# RS232.net
KiCad netlist of a schematic drawn in Altium Designer
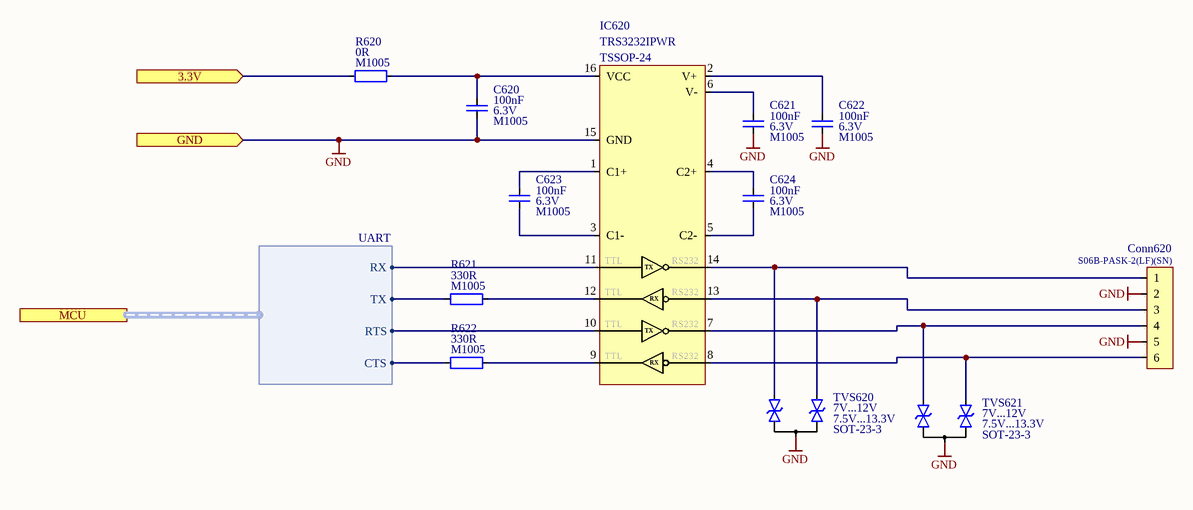
[diagram p0: RS232.SchDoc]

(export (version "E")
  (design (tool "Eeschema 10.0.6"))
  (components
    (comp (ref "C620")
      (value "100nF")
      (footprint "Capacitor_Ceramic_M1005_I0402")
      (description "Cap, Cer, 100nF, 6.3V, M1005")
      (fields
        (field (name "VOLTAGE") "6.3V")
        (field (name "MANUFACTURER PART NUMBER") "04026D104KAT4A")
        (field (name "MANUFACTURER") "Kyocera")
        (field (name "PACKAGE") "M1005")
      )
      (libsource (lib "Capacitor") (part "Capacitor_Ceramic"))
    )
    (comp (ref "C621")
      (value "100nF")
      (footprint "Capacitor_Ceramic_M1005_I0402")
      (description "Cap, Cer, 100nF, 6.3V, M1005")
      (fields
        (field (name "VOLTAGE") "6.3V")
        (field (name "MANUFACTURER PART NUMBER") "04026D104KAT4A")
        (field (name "MANUFACTURER") "Kyocera")
        (field (name "PACKAGE") "M1005")
      )
      (libsource (lib "Capacitor") (part "Capacitor_Ceramic"))
    )
    (comp (ref "C622")
      (value "100nF")
      (footprint "Capacitor_Ceramic_M1005_I0402")
      (description "Cap, Cer, 100nF, 6.3V, M1005")
      (fields
        (field (name "VOLTAGE") "6.3V")
        (field (name "MANUFACTURER PART NUMBER") "04026D104KAT4A")
        (field (name "MANUFACTURER") "Kyocera")
        (field (name "PACKAGE") "M1005")
      )
      (libsource (lib "Capacitor") (part "Capacitor_Ceramic"))
    )
    (comp (ref "C623")
      (value "100nF")
      (footprint "Capacitor_Ceramic_M1005_I0402")
      (description "Cap, Cer, 100nF, 6.3V, M1005")
      (fields
        (field (name "VOLTAGE") "6.3V")
        (field (name "MANUFACTURER PART NUMBER") "04026D104KAT4A")
        (field (name "MANUFACTURER") "Kyocera")
        (field (name "PACKAGE") "M1005")
      )
      (libsource (lib "Capacitor") (part "Capacitor_Ceramic"))
    )
    (comp (ref "C624")
      (value "100nF")
      (footprint "Capacitor_Ceramic_M1005_I0402")
      (description "Cap, Cer, 100nF, 6.3V, M1005")
      (fields
        (field (name "VOLTAGE") "6.3V")
        (field (name "MANUFACTURER PART NUMBER") "04026D104KAT4A")
        (field (name "MANUFACTURER") "Kyocera")
        (field (name "PACKAGE") "M1005")
      )
      (libsource (lib "Capacitor") (part "Capacitor_Ceramic"))
    )
    (comp (ref "Conn620")
      (value "Connector - 6P")
      (footprint "Connector, S06B-PASK-2")
      (description "Conn, JST, 6P, TH, PA, Side Entry")
      (fields
        (field (name "MANUFACTURER") "JST")
        (field (name "MANUFACTURER PART NUMBER") "S06B-PASK-2(LF)(SN)")
      )
      (libsource (lib "Connector - JST") (part "Connector - 6P"))
    )
    (comp (ref "IC620")
      (value "RS232 - Texas, TRS3232IPWR")
      (footprint "TSSOP-16")
      (description "IC, Interface, RS232, TSSOP-24")
      (fields
        (field (name "MANUFACTURER") "Texas")
        (field (name "MANUFACTURER PART NUMBER") "TRS3232IPWR")
        (field (name "PACKAGE") "TSSOP-24")
      )
      (libsource (lib "IC-Interface") (part "RS232 - Texas, TRS3232IPWR"))
    )
    (comp (ref "R620")
      (value "0R")
      (footprint "Resistor_Smd_M1005_I0402")
      (description "Res, 0R, M1005")
      (fields
        (field (name "MANUFACTURER") "Yageo")
        (field (name "MANUFACTURER PART NUMBER") "RC0402FR-070RL")
        (field (name "PACKAGE") "M1005")
      )
      (libsource (lib "Resistor") (part "Resistor"))
    )
    (comp (ref "R621")
      (value "330R")
      (footprint "Resistor_Smd_M1005_I0402")
      (description "Res, 330R, 1%, M1005")
      (fields
        (field (name "TOLERANCE") "1%")
        (field (name "MANUFACTURER") "Yageo")
        (field (name "PACKAGE") "M1005")
      )
      (libsource (lib "Resistor") (part "Resistor"))
    )
    (comp (ref "R622")
      (value "330R")
      (footprint "Resistor_Smd_M1005_I0402")
      (description "Res, 330R, 1%, M1005")
      (fields
        (field (name "TOLERANCE") "1%")
        (field (name "MANUFACTURER") "Yageo")
        (field (name "PACKAGE") "M1005")
      )
      (libsource (lib "Resistor") (part "Resistor"))
    )
    (comp (ref "TVS620")
      (value "Diode_Tvs_2P_Bidirectional")
      (footprint "Diode_SOT-23-3_2P_Bidirectional_Type_1")
      (description "TVS, 2P, Bidirectional, 7V/12V, SOT-23-3")
      (fields
        (field (name "MANUFACTURER PART NUMBER") "CDSOT23-SM712")
        (field (name "MANUFACTURER") "Bourns")
        (field (name "VOLTAGE, BREAK DOWN") "7.5V...13.3V")
        (field (name "VOLTAGE, STAND OFF") "7V...12V")
        (field (name "PACKAGE") "SOT-23-3")
      )
      (libsource (lib "Diode") (part "Diode_Tvs_2P_Bidirectional"))
    )
    (comp (ref "TVS621")
      (value "Diode_Tvs_2P_Bidirectional")
      (footprint "Diode_SOT-23-3_2P_Bidirectional_Type_1")
      (description "TVS, 2P, Bidirectional, 7V/12V, SOT-23-3")
      (fields
        (field (name "MANUFACTURER PART NUMBER") "CDSOT23-SM712")
        (field (name "MANUFACTURER") "Bourns")
        (field (name "VOLTAGE, BREAK DOWN") "7.5V...13.3V")
        (field (name "VOLTAGE, STAND OFF") "7V...12V")
        (field (name "PACKAGE") "SOT-23-3")
      )
      (libsource (lib "Diode") (part "Diode_Tvs_2P_Bidirectional"))
    )
  )
  (nets
    (net (code "2") (name "/3.3V") (class "Default")
      (node (ref "R620") (pin "1") (pinfunction "1_1") (pintype "passive"))
    )
    (net (code "3") (name "/CTS") (class "Default")
      (node (ref "R622") (pin "1") (pinfunction "1_1") (pintype "passive"))
    )
    (net (code "4") (name "/RTS") (class "Default")
      (node (ref "IC620") (pin "10") (pinfunction "DIN2_10") (pintype "passive"))
    )
    (net (code "5") (name "/RX") (class "Default")
      (node (ref "IC620") (pin "11") (pinfunction "DIN1_11") (pintype "passive"))
    )
    (net (code "6") (name "/TX") (class "Default")
      (node (ref "R621") (pin "1") (pinfunction "1_1") (pintype "passive"))
    )
    (net (code "8") (name "GND") (class "Default")
      (node (ref "C620") (pin "2") (pinfunction "2_2") (pintype "passive"))
      (node (ref "C621") (pin "2") (pinfunction "2_2") (pintype "passive"))
      (node (ref "C622") (pin "2") (pinfunction "2_2") (pintype "passive"))
      (node (ref "Conn620") (pin "2") (pinfunction "2_2") (pintype "passive"))
      (node (ref "Conn620") (pin "5") (pinfunction "5_5") (pintype "passive"))
      (node (ref "IC620") (pin "15") (pinfunction "GND_15") (pintype "passive"))
      (node (ref "TVS620") (pin "Common") (pinfunction "Common_Common") (pintype "passive"))
      (node (ref "TVS621") (pin "Common") (pinfunction "Common_Common") (pintype "passive"))
    )
    (net (code "9") (name "Net-(IC620-C1+)") (class "Default")
      (node (ref "C623") (pin "1") (pinfunction "1_1") (pintype "passive"))
      (node (ref "IC620") (pin "1") (pinfunction "C1+_1") (pintype "passive"))
    )
    (net (code "10") (name "Net-(IC620-C1-)") (class "Default")
      (node (ref "C623") (pin "2") (pinfunction "2_2") (pintype "passive"))
      (node (ref "IC620") (pin "3") (pinfunction "C1-_3") (pintype "passive"))
    )
    (net (code "11") (name "Net-(IC620-C2+)") (class "Default")
      (node (ref "C624") (pin "1") (pinfunction "1_1") (pintype "passive"))
      (node (ref "IC620") (pin "4") (pinfunction "C2+_4") (pintype "passive"))
    )
    (net (code "12") (name "Net-(IC620-C2-)") (class "Default")
      (node (ref "C624") (pin "2") (pinfunction "2_2") (pintype "passive"))
      (node (ref "IC620") (pin "5") (pinfunction "C2-_5") (pintype "passive"))
    )
    (net (code "13") (name "Net-(IC620-DOUT1)") (class "Default")
      (node (ref "Conn620") (pin "1") (pinfunction "1_1") (pintype "passive"))
      (node (ref "IC620") (pin "14") (pinfunction "DOUT1_14") (pintype "passive"))
      (node (ref "TVS620") (pin "D1") (pinfunction "D1_D1") (pintype "passive"))
    )
    (net (code "14") (name "Net-(IC620-DOUT2)") (class "Default")
      (node (ref "Conn620") (pin "4") (pinfunction "4_4") (pintype "passive"))
      (node (ref "IC620") (pin "7") (pinfunction "DOUT2_7") (pintype "passive"))
      (node (ref "TVS621") (pin "D1") (pinfunction "D1_D1") (pintype "passive"))
    )
    (net (code "15") (name "Net-(IC620-RIN1)") (class "Default")
      (node (ref "Conn620") (pin "3") (pinfunction "3_3") (pintype "passive"))
      (node (ref "IC620") (pin "13") (pinfunction "RIN1_13") (pintype "passive"))
      (node (ref "TVS620") (pin "D2") (pinfunction "D2_D2") (pintype "passive"))
    )
    (net (code "16") (name "Net-(IC620-RIN2)") (class "Default")
      (node (ref "Conn620") (pin "6") (pinfunction "6_6") (pintype "passive"))
      (node (ref "IC620") (pin "8") (pinfunction "RIN2_8") (pintype "passive"))
      (node (ref "TVS621") (pin "D2") (pinfunction "D2_D2") (pintype "passive"))
    )
    (net (code "17") (name "Net-(IC620-ROUT1)") (class "Default")
      (node (ref "IC620") (pin "12") (pinfunction "ROUT1_12") (pintype "passive"))
      (node (ref "R621") (pin "2") (pinfunction "2_2") (pintype "passive"))
    )
    (net (code "18") (name "Net-(IC620-ROUT2)") (class "Default")
      (node (ref "IC620") (pin "9") (pinfunction "ROUT2_9") (pintype "passive"))
      (node (ref "R622") (pin "2") (pinfunction "2_2") (pintype "passive"))
    )
    (net (code "19") (name "Net-(IC620-V+)") (class "Default")
      (node (ref "C622") (pin "1") (pinfunction "1_1") (pintype "passive"))
      (node (ref "IC620") (pin "2") (pinfunction "V+_2") (pintype "passive"))
    )
    (net (code "20") (name "Net-(IC620-V-)") (class "Default")
      (node (ref "C621") (pin "1") (pinfunction "1_1") (pintype "passive"))
      (node (ref "IC620") (pin "6") (pinfunction "V-_6") (pintype "passive"))
    )
    (net (code "21") (name "Net-(IC620-VCC)") (class "Default")
      (node (ref "C620") (pin "1") (pinfunction "1_1") (pintype "passive"))
      (node (ref "IC620") (pin "16") (pinfunction "VCC_16") (pintype "passive"))
      (node (ref "R620") (pin "2") (pinfunction "2_2") (pintype "passive"))
    )
  )
)
